# LCD.net
KiCad netlist of a schematic drawn in Altium Designer
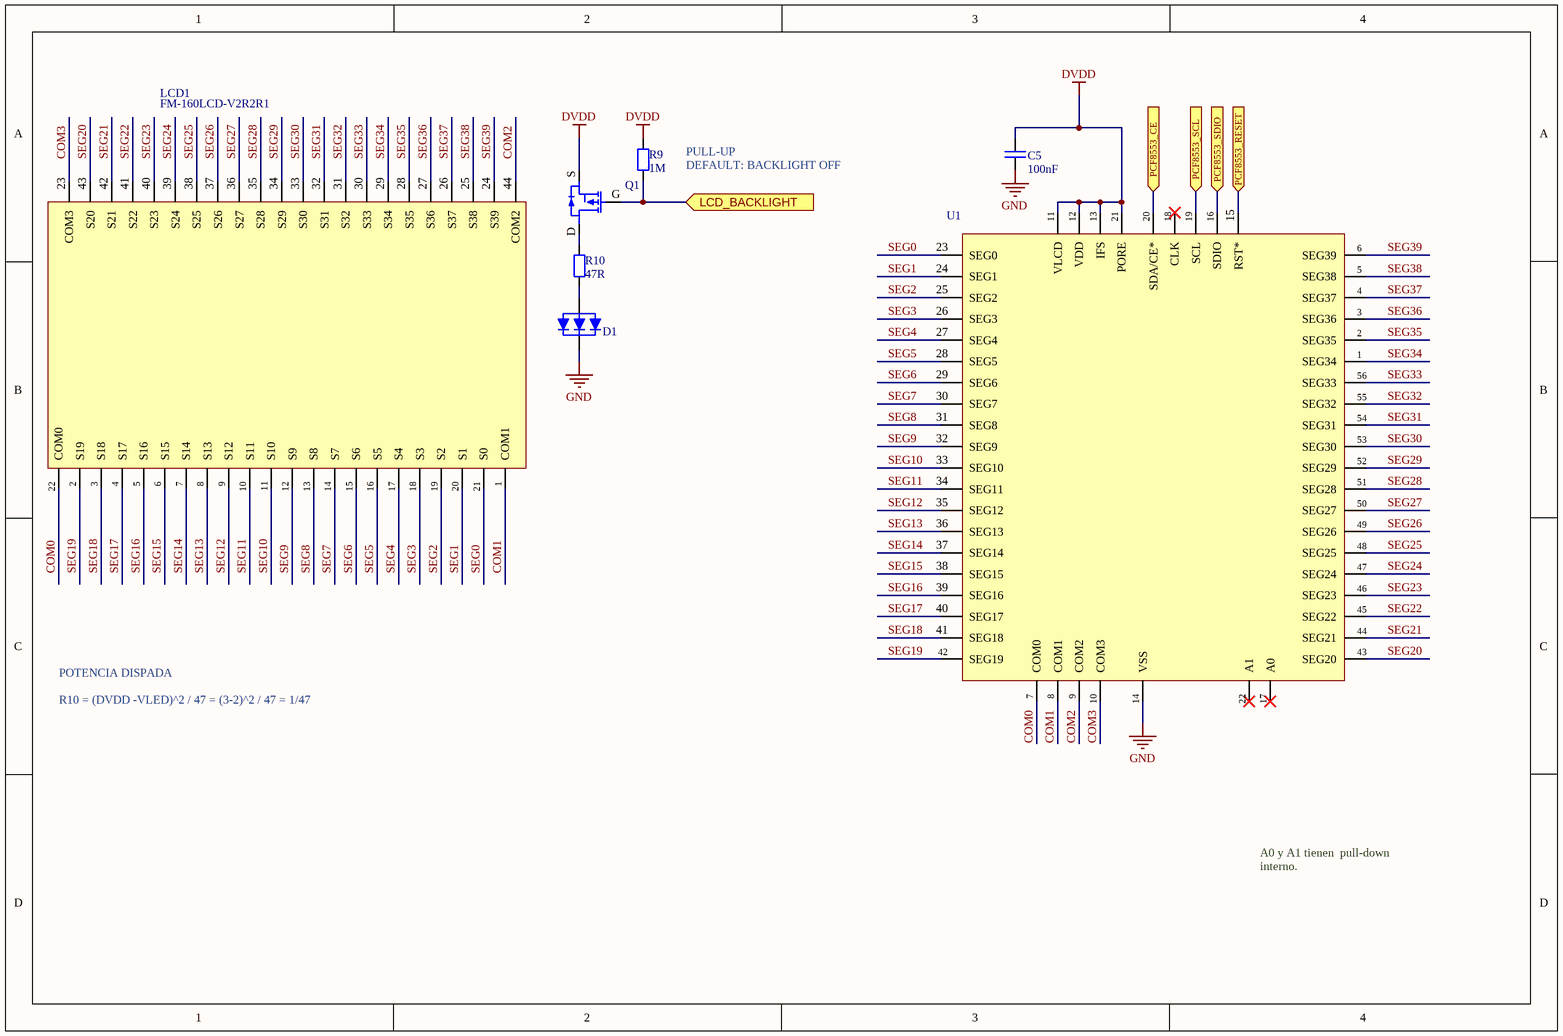
[diagram p0: LCD.SchDoc]

(export (version "E")
  (design (tool "Eeschema 10.0.6"))
  (components
    (comp (ref "C5")
      (value "100nF")
      (footprint "CAP_SM0805_YAGEOCC2_N")
      (description "CAP 100nF SM0805 X7R 25V YAGEO CC2")
      (fields
        (field (name "MANUFACTURER") "Yageo")
        (field (name "MANUFACTURER PART NUMBER") "CC0805KRX7R8BB104")
      )
      (libsource (lib "Yageo") (part "CC0805KRX7R8BB104"))
    )
    (comp (ref "D1")
      (value "BACKLIGHT")
      (footprint "BACKLIGHT")
      (description "IF=45mA;VF=3V")
      (fields
        (field (name "MANUFACTURER") "FLOWMEET")
        (field (name "MANUFACTURER PART NUMBER") "FM-160-BACKLIGHT")
      )
      (libsource (lib "FM-160LCD") (part "FM-160-BACKLIGHT"))
    )
    (comp (ref "LCD1")
      (value "FM-160LCD-V2R2R1")
      (footprint "FMC-160LCD V2")
      (fields (field (name "MANUFACTURER") "FLOWMEET"))
      (libsource (lib "FM-160LCD") (part "FM-160LCD-V2R2R1"))
    )
    (comp (ref "Q1")
      (value "DMG3401LSN-7")
      (footprint "DMG3401LSN-7")
      (description "P-CHANNEL ENHANCEMENT MODE MOSFET\r\nRDS(ON) = 85mΩ @ VGS = -2.5V -> ID -2.7A\r\nV(BR)DDS 30V")
      (fields (field (name "MANUFACTURER") "Diodes Incorporated"))
      (libsource (lib "mosfet") (part "DMG3401LSN-7"))
    )
    (comp (ref "R9")
      (value "1M")
      (footprint "RES_SM0805_YAGEORC_N")
      (description "RES 1M SM0805 YAGEO RC_L")
      (fields
        (field (name "MANUFACTURER") "Yageo")
        (field (name "MANUFACTURER PART NUMBER") "RC0805FR-071ML")
      )
      (libsource (lib "Yageo") (part "RC0805FR-071ML"))
    )
    (comp (ref "R10")
      (value "47R")
      (footprint "RES_SM0805_YAGEORC_N")
      (description "RES 47R SM0805 YAGEO RC_L")
      (fields
        (field (name "MANUFACTURER") "Yageo")
        (field (name "MANUFACTURER PART NUMBER") "RC0805FR-0747RL")
      )
      (libsource (lib "Yageo") (part "RC0805FR-0747RL"))
    )
    (comp (ref "U1")
      (value "PCF8553DTT/AY")
      (footprint "LCD DRIVER - TSSOP56")
      (description "40 × 4 LCD SEGMENT DRIVER")
      (fields (field (name "MANUFACTURER") "NXP"))
      (libsource (lib "LCD_drivers") (part "PCF8553DTT/AY"))
    )
  )
  (nets
    (net (code "1") (name "/COM0") (class "Default")
      (node (ref "LCD1") (pin "22") (pinfunction "COM0_22") (pintype "passive"))
      (node (ref "U1") (pin "7") (pinfunction "COM0_7") (pintype "passive"))
    )
    (net (code "2") (name "/COM1") (class "Default")
      (node (ref "LCD1") (pin "1") (pinfunction "COM1_1") (pintype "passive"))
      (node (ref "U1") (pin "8") (pinfunction "COM1_8") (pintype "passive"))
    )
    (net (code "3") (name "/COM2") (class "Default")
      (node (ref "LCD1") (pin "44") (pinfunction "COM2_44") (pintype "passive"))
      (node (ref "U1") (pin "9") (pinfunction "COM2_9") (pintype "passive"))
    )
    (net (code "4") (name "/COM3") (class "Default")
      (node (ref "LCD1") (pin "23") (pinfunction "COM3_23") (pintype "passive"))
      (node (ref "U1") (pin "10") (pinfunction "COM3_10") (pintype "passive"))
    )
    (net (code "5") (name "/LCD_BACKLIGHT") (class "Default")
      (node (ref "Q1") (pin "G") (pinfunction "G_G") (pintype "passive"))
      (node (ref "R9") (pin "1") (pintype "passive"))
    )
    (net (code "6") (name "/PCF8553_CE") (class "Default")
      (node (ref "U1") (pin "20") (pinfunction "SDA/CE*_20") (pintype "passive"))
    )
    (net (code "7") (name "/PCF8553_RESET") (class "Default")
      (node (ref "U1") (pin "15") (pinfunction "RST*_15") (pintype "passive"))
    )
    (net (code "8") (name "/PCF8553_SCL") (class "Default")
      (node (ref "U1") (pin "19") (pinfunction "SCL_19") (pintype "passive"))
    )
    (net (code "9") (name "/PCF8553_SDIO") (class "Default")
      (node (ref "U1") (pin "16") (pinfunction "SDIO_16") (pintype "passive"))
    )
    (net (code "10") (name "/SEG0") (class "Default")
      (node (ref "LCD1") (pin "21") (pinfunction "S0_21") (pintype "passive"))
      (node (ref "U1") (pin "23") (pinfunction "SEG0_23") (pintype "passive"))
    )
    (net (code "11") (name "/SEG1") (class "Default")
      (node (ref "LCD1") (pin "20") (pinfunction "S1_20") (pintype "passive"))
      (node (ref "U1") (pin "24") (pinfunction "SEG1_24") (pintype "passive"))
    )
    (net (code "12") (name "/SEG2") (class "Default")
      (node (ref "LCD1") (pin "19") (pinfunction "S2_19") (pintype "passive"))
      (node (ref "U1") (pin "25") (pinfunction "SEG2_25") (pintype "passive"))
    )
    (net (code "13") (name "/SEG3") (class "Default")
      (node (ref "LCD1") (pin "18") (pinfunction "S3_18") (pintype "passive"))
      (node (ref "U1") (pin "26") (pinfunction "SEG3_26") (pintype "passive"))
    )
    (net (code "14") (name "/SEG4") (class "Default")
      (node (ref "LCD1") (pin "17") (pinfunction "S4_17") (pintype "passive"))
      (node (ref "U1") (pin "27") (pinfunction "SEG4_27") (pintype "passive"))
    )
    (net (code "15") (name "/SEG5") (class "Default")
      (node (ref "LCD1") (pin "16") (pinfunction "S5_16") (pintype "passive"))
      (node (ref "U1") (pin "28") (pinfunction "SEG5_28") (pintype "passive"))
    )
    (net (code "16") (name "/SEG6") (class "Default")
      (node (ref "LCD1") (pin "15") (pinfunction "S6_15") (pintype "passive"))
      (node (ref "U1") (pin "29") (pinfunction "SEG6_29") (pintype "passive"))
    )
    (net (code "17") (name "/SEG7") (class "Default")
      (node (ref "LCD1") (pin "14") (pinfunction "S7_14") (pintype "passive"))
      (node (ref "U1") (pin "30") (pinfunction "SEG7_30") (pintype "passive"))
    )
    (net (code "18") (name "/SEG8") (class "Default")
      (node (ref "LCD1") (pin "13") (pinfunction "S8_13") (pintype "passive"))
      (node (ref "U1") (pin "31") (pinfunction "SEG8_31") (pintype "passive"))
    )
    (net (code "19") (name "/SEG9") (class "Default")
      (node (ref "LCD1") (pin "12") (pinfunction "S9_12") (pintype "passive"))
      (node (ref "U1") (pin "32") (pinfunction "SEG9_32") (pintype "passive"))
    )
    (net (code "20") (name "/SEG10") (class "Default")
      (node (ref "LCD1") (pin "11") (pinfunction "S10_11") (pintype "passive"))
      (node (ref "U1") (pin "33") (pinfunction "SEG10_33") (pintype "passive"))
    )
    (net (code "21") (name "/SEG11") (class "Default")
      (node (ref "LCD1") (pin "10") (pinfunction "S11_10") (pintype "passive"))
      (node (ref "U1") (pin "34") (pinfunction "SEG11_34") (pintype "passive"))
    )
    (net (code "22") (name "/SEG12") (class "Default")
      (node (ref "LCD1") (pin "9") (pinfunction "S12_9") (pintype "passive"))
      (node (ref "U1") (pin "35") (pinfunction "SEG12_35") (pintype "passive"))
    )
    (net (code "23") (name "/SEG13") (class "Default")
      (node (ref "LCD1") (pin "8") (pinfunction "S13_8") (pintype "passive"))
      (node (ref "U1") (pin "36") (pinfunction "SEG13_36") (pintype "passive"))
    )
    (net (code "24") (name "/SEG14") (class "Default")
      (node (ref "LCD1") (pin "7") (pinfunction "S14_7") (pintype "passive"))
      (node (ref "U1") (pin "37") (pinfunction "SEG14_37") (pintype "passive"))
    )
    (net (code "25") (name "/SEG15") (class "Default")
      (node (ref "LCD1") (pin "6") (pinfunction "S15_6") (pintype "passive"))
      (node (ref "U1") (pin "38") (pinfunction "SEG15_38") (pintype "passive"))
    )
    (net (code "26") (name "/SEG16") (class "Default")
      (node (ref "LCD1") (pin "5") (pinfunction "S16_5") (pintype "passive"))
      (node (ref "U1") (pin "39") (pinfunction "SEG16_39") (pintype "passive"))
    )
    (net (code "27") (name "/SEG17") (class "Default")
      (node (ref "LCD1") (pin "4") (pinfunction "S17_4") (pintype "passive"))
      (node (ref "U1") (pin "40") (pinfunction "SEG17_40") (pintype "passive"))
    )
    (net (code "28") (name "/SEG18") (class "Default")
      (node (ref "LCD1") (pin "3") (pinfunction "S18_3") (pintype "passive"))
      (node (ref "U1") (pin "41") (pinfunction "SEG18_41") (pintype "passive"))
    )
    (net (code "29") (name "/SEG19") (class "Default")
      (node (ref "LCD1") (pin "2") (pinfunction "S19_2") (pintype "passive"))
      (node (ref "U1") (pin "42") (pinfunction "SEG19_42") (pintype "passive"))
    )
    (net (code "30") (name "/SEG20") (class "Default")
      (node (ref "LCD1") (pin "43") (pinfunction "S20_43") (pintype "passive"))
      (node (ref "U1") (pin "43") (pinfunction "SEG20_43") (pintype "passive"))
    )
    (net (code "31") (name "/SEG21") (class "Default")
      (node (ref "LCD1") (pin "42") (pinfunction "S21_42") (pintype "passive"))
      (node (ref "U1") (pin "44") (pinfunction "SEG21_44") (pintype "passive"))
    )
    (net (code "32") (name "/SEG22") (class "Default")
      (node (ref "LCD1") (pin "41") (pinfunction "S22_41") (pintype "passive"))
      (node (ref "U1") (pin "45") (pinfunction "SEG22_45") (pintype "passive"))
    )
    (net (code "33") (name "/SEG23") (class "Default")
      (node (ref "LCD1") (pin "40") (pinfunction "S23_40") (pintype "passive"))
      (node (ref "U1") (pin "46") (pinfunction "SEG23_46") (pintype "passive"))
    )
    (net (code "34") (name "/SEG24") (class "Default")
      (node (ref "LCD1") (pin "39") (pinfunction "S24_39") (pintype "passive"))
      (node (ref "U1") (pin "47") (pinfunction "SEG24_47") (pintype "passive"))
    )
    (net (code "35") (name "/SEG25") (class "Default")
      (node (ref "LCD1") (pin "38") (pinfunction "S25_38") (pintype "passive"))
      (node (ref "U1") (pin "48") (pinfunction "SEG25_48") (pintype "passive"))
    )
    (net (code "36") (name "/SEG26") (class "Default")
      (node (ref "LCD1") (pin "37") (pinfunction "S26_37") (pintype "passive"))
      (node (ref "U1") (pin "49") (pinfunction "SEG26_49") (pintype "passive"))
    )
    (net (code "37") (name "/SEG27") (class "Default")
      (node (ref "LCD1") (pin "36") (pinfunction "S27_36") (pintype "passive"))
      (node (ref "U1") (pin "50") (pinfunction "SEG27_50") (pintype "passive"))
    )
    (net (code "38") (name "/SEG28") (class "Default")
      (node (ref "LCD1") (pin "35") (pinfunction "S28_35") (pintype "passive"))
      (node (ref "U1") (pin "51") (pinfunction "SEG28_51") (pintype "passive"))
    )
    (net (code "39") (name "/SEG29") (class "Default")
      (node (ref "LCD1") (pin "34") (pinfunction "S29_34") (pintype "passive"))
      (node (ref "U1") (pin "52") (pinfunction "SEG29_52") (pintype "passive"))
    )
    (net (code "40") (name "/SEG30") (class "Default")
      (node (ref "LCD1") (pin "33") (pinfunction "S30_33") (pintype "passive"))
      (node (ref "U1") (pin "53") (pinfunction "SEG30_53") (pintype "passive"))
    )
    (net (code "41") (name "/SEG31") (class "Default")
      (node (ref "LCD1") (pin "32") (pinfunction "S31_32") (pintype "passive"))
      (node (ref "U1") (pin "54") (pinfunction "SEG31_54") (pintype "passive"))
    )
    (net (code "42") (name "/SEG32") (class "Default")
      (node (ref "LCD1") (pin "31") (pinfunction "S32_31") (pintype "passive"))
      (node (ref "U1") (pin "55") (pinfunction "SEG32_55") (pintype "passive"))
    )
    (net (code "43") (name "/SEG33") (class "Default")
      (node (ref "LCD1") (pin "30") (pinfunction "S33_30") (pintype "passive"))
      (node (ref "U1") (pin "56") (pinfunction "SEG33_56") (pintype "passive"))
    )
    (net (code "44") (name "/SEG34") (class "Default")
      (node (ref "LCD1") (pin "29") (pinfunction "S34_29") (pintype "passive"))
      (node (ref "U1") (pin "1") (pinfunction "SEG34_1") (pintype "passive"))
    )
    (net (code "45") (name "/SEG35") (class "Default")
      (node (ref "LCD1") (pin "28") (pinfunction "S35_28") (pintype "passive"))
      (node (ref "U1") (pin "2") (pinfunction "SEG35_2") (pintype "passive"))
    )
    (net (code "46") (name "/SEG36") (class "Default")
      (node (ref "LCD1") (pin "27") (pinfunction "S36_27") (pintype "passive"))
      (node (ref "U1") (pin "3") (pinfunction "SEG36_3") (pintype "passive"))
    )
    (net (code "47") (name "/SEG37") (class "Default")
      (node (ref "LCD1") (pin "26") (pinfunction "S37_26") (pintype "passive"))
      (node (ref "U1") (pin "4") (pinfunction "SEG37_4") (pintype "passive"))
    )
    (net (code "48") (name "/SEG38") (class "Default")
      (node (ref "LCD1") (pin "25") (pinfunction "S38_25") (pintype "passive"))
      (node (ref "U1") (pin "5") (pinfunction "SEG38_5") (pintype "passive"))
    )
    (net (code "49") (name "/SEG39") (class "Default")
      (node (ref "LCD1") (pin "24") (pinfunction "S39_24") (pintype "passive"))
      (node (ref "U1") (pin "6") (pinfunction "SEG39_6") (pintype "passive"))
    )
    (net (code "50") (name "DVDD") (class "Default")
      (node (ref "C5") (pin "1") (pintype "passive"))
      (node (ref "Q1") (pin "S") (pinfunction "S_S") (pintype "passive"))
      (node (ref "R9") (pin "2") (pintype "passive"))
      (node (ref "U1") (pin "11") (pinfunction "VLCD_11") (pintype "passive"))
      (node (ref "U1") (pin "12") (pinfunction "VDD_12") (pintype "passive"))
      (node (ref "U1") (pin "13") (pinfunction "IFS_13") (pintype "passive"))
      (node (ref "U1") (pin "21") (pinfunction "PORE_21") (pintype "passive"))
    )
    (net (code "51") (name "GND") (class "Default")
      (node (ref "C5") (pin "2") (pintype "passive"))
      (node (ref "D1") (pin "2") (pinfunction "0_2") (pintype "passive"))
      (node (ref "U1") (pin "14") (pinfunction "VSS_14") (pintype "passive"))
    )
    (net (code "52") (name "Net-(D1-Pad1)") (class "Default")
      (node (ref "D1") (pin "1") (pinfunction "1_1") (pintype "passive"))
      (node (ref "R10") (pin "1") (pintype "passive"))
    )
    (net (code "53") (name "Net-(Q1-PadD)") (class "Default")
      (node (ref "Q1") (pin "D") (pinfunction "D_D") (pintype "passive"))
      (node (ref "R10") (pin "2") (pintype "passive"))
    )
    (net (code "54") (name "unconnected-(U1-A0-Pad17)") (class "Default")
      (node (ref "U1") (pin "17") (pinfunction "A0_17") (pintype "passive+no_connect"))
    )
    (net (code "55") (name "unconnected-(U1-A1-Pad22)") (class "Default")
      (node (ref "U1") (pin "22") (pinfunction "A1_22") (pintype "passive+no_connect"))
    )
    (net (code "56") (name "unconnected-(U1-CLK-Pad18)") (class "Default")
      (node (ref "U1") (pin "18") (pinfunction "CLK_18") (pintype "passive+no_connect"))
    )
  )
)
